# main.net
KiCad netlist of a schematic drawn in Altium Designer
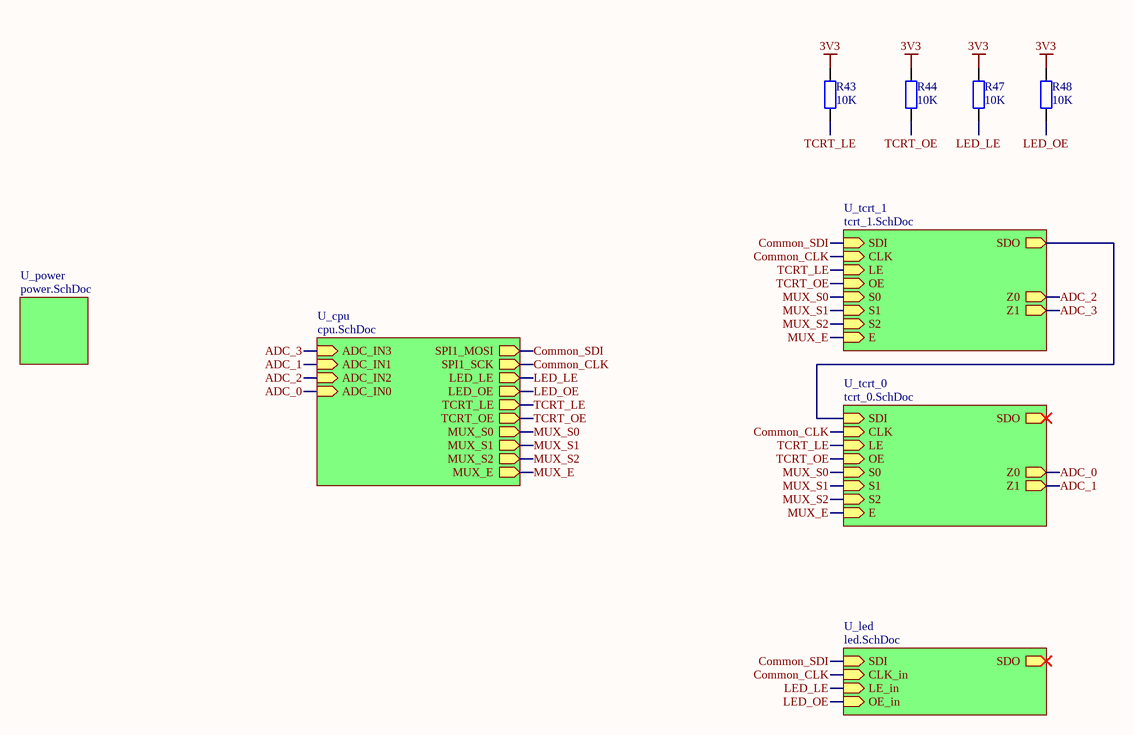
[diagram p0: main.SchDoc]

(export (version "E")
  (design (tool "Eeschema 10.0.6"))
  (components
    (comp (ref "R43")
      (value "10K")
      (footprint "FP_0805_RES")
      (description "Resistor")
      (libsource (lib "hallglib") (part "RES"))
    )
    (comp (ref "R44")
      (value "10K")
      (footprint "FP_0805_RES")
      (description "Resistor")
      (libsource (lib "hallglib") (part "RES"))
    )
    (comp (ref "R47")
      (value "10K")
      (footprint "FP_0805_RES")
      (description "Resistor")
      (libsource (lib "hallglib") (part "RES"))
    )
    (comp (ref "R48")
      (value "10K")
      (footprint "FP_0805_RES")
      (description "Resistor")
      (libsource (lib "hallglib") (part "RES"))
    )
  )
  (nets
    (net (code "7") (name "/LED_LE") (class "Default")
      (node (ref "R47") (pin "1") (pinfunction "1_1") (pintype "passive"))
    )
    (net (code "8") (name "/LED_OE") (class "Default")
      (node (ref "R48") (pin "1") (pinfunction "1_1") (pintype "passive"))
    )
    (net (code "16") (name "/TCRT_LE") (class "Default")
      (node (ref "R43") (pin "1") (pinfunction "1_1") (pintype "passive"))
    )
    (net (code "17") (name "/TCRT_OE") (class "Default")
      (node (ref "R44") (pin "1") (pinfunction "1_1") (pintype "passive"))
    )
    (net (code "18") (name "3V3") (class "Default")
      (node (ref "R43") (pin "2") (pinfunction "2_2") (pintype "passive"))
      (node (ref "R44") (pin "2") (pinfunction "2_2") (pintype "passive"))
      (node (ref "R47") (pin "2") (pinfunction "2_2") (pintype "passive"))
      (node (ref "R48") (pin "2") (pinfunction "2_2") (pintype "passive"))
    )
  )
)
